# vape_v3_logic.net
KiCad netlist of a schematic drawn in EAGLE
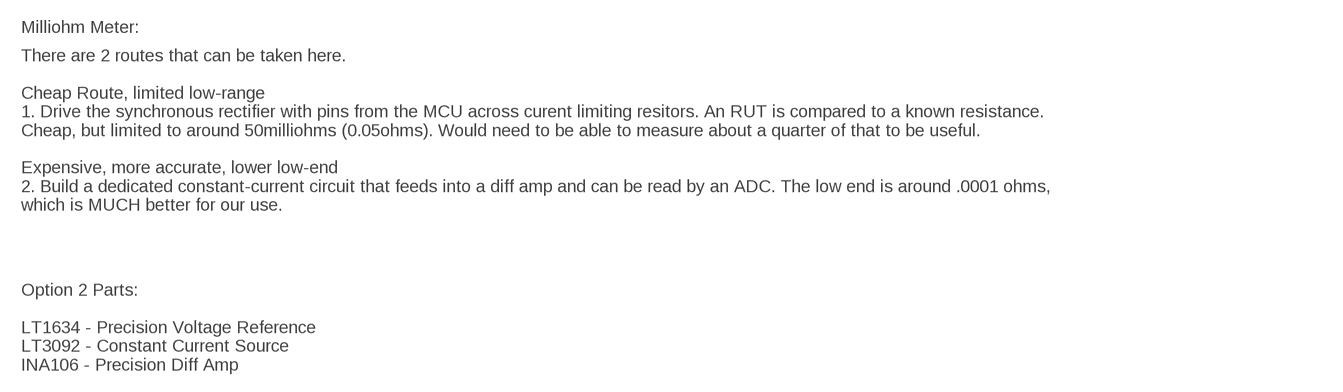
[diagram p0: schematic, sheet 1]
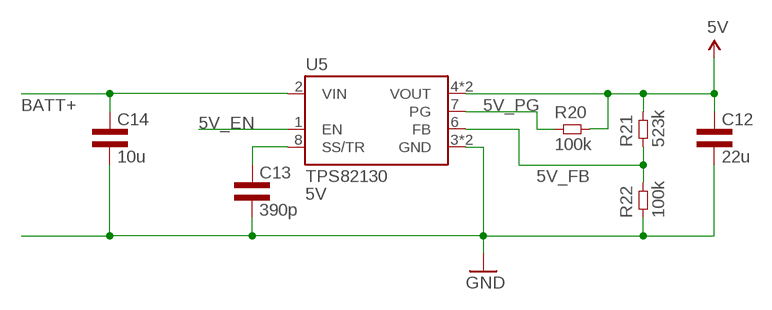
[diagram p1: schematic, sheet 2]
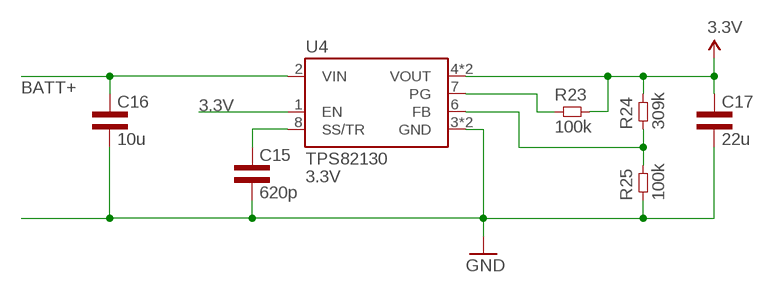
[diagram p2: schematic, sheet 3]
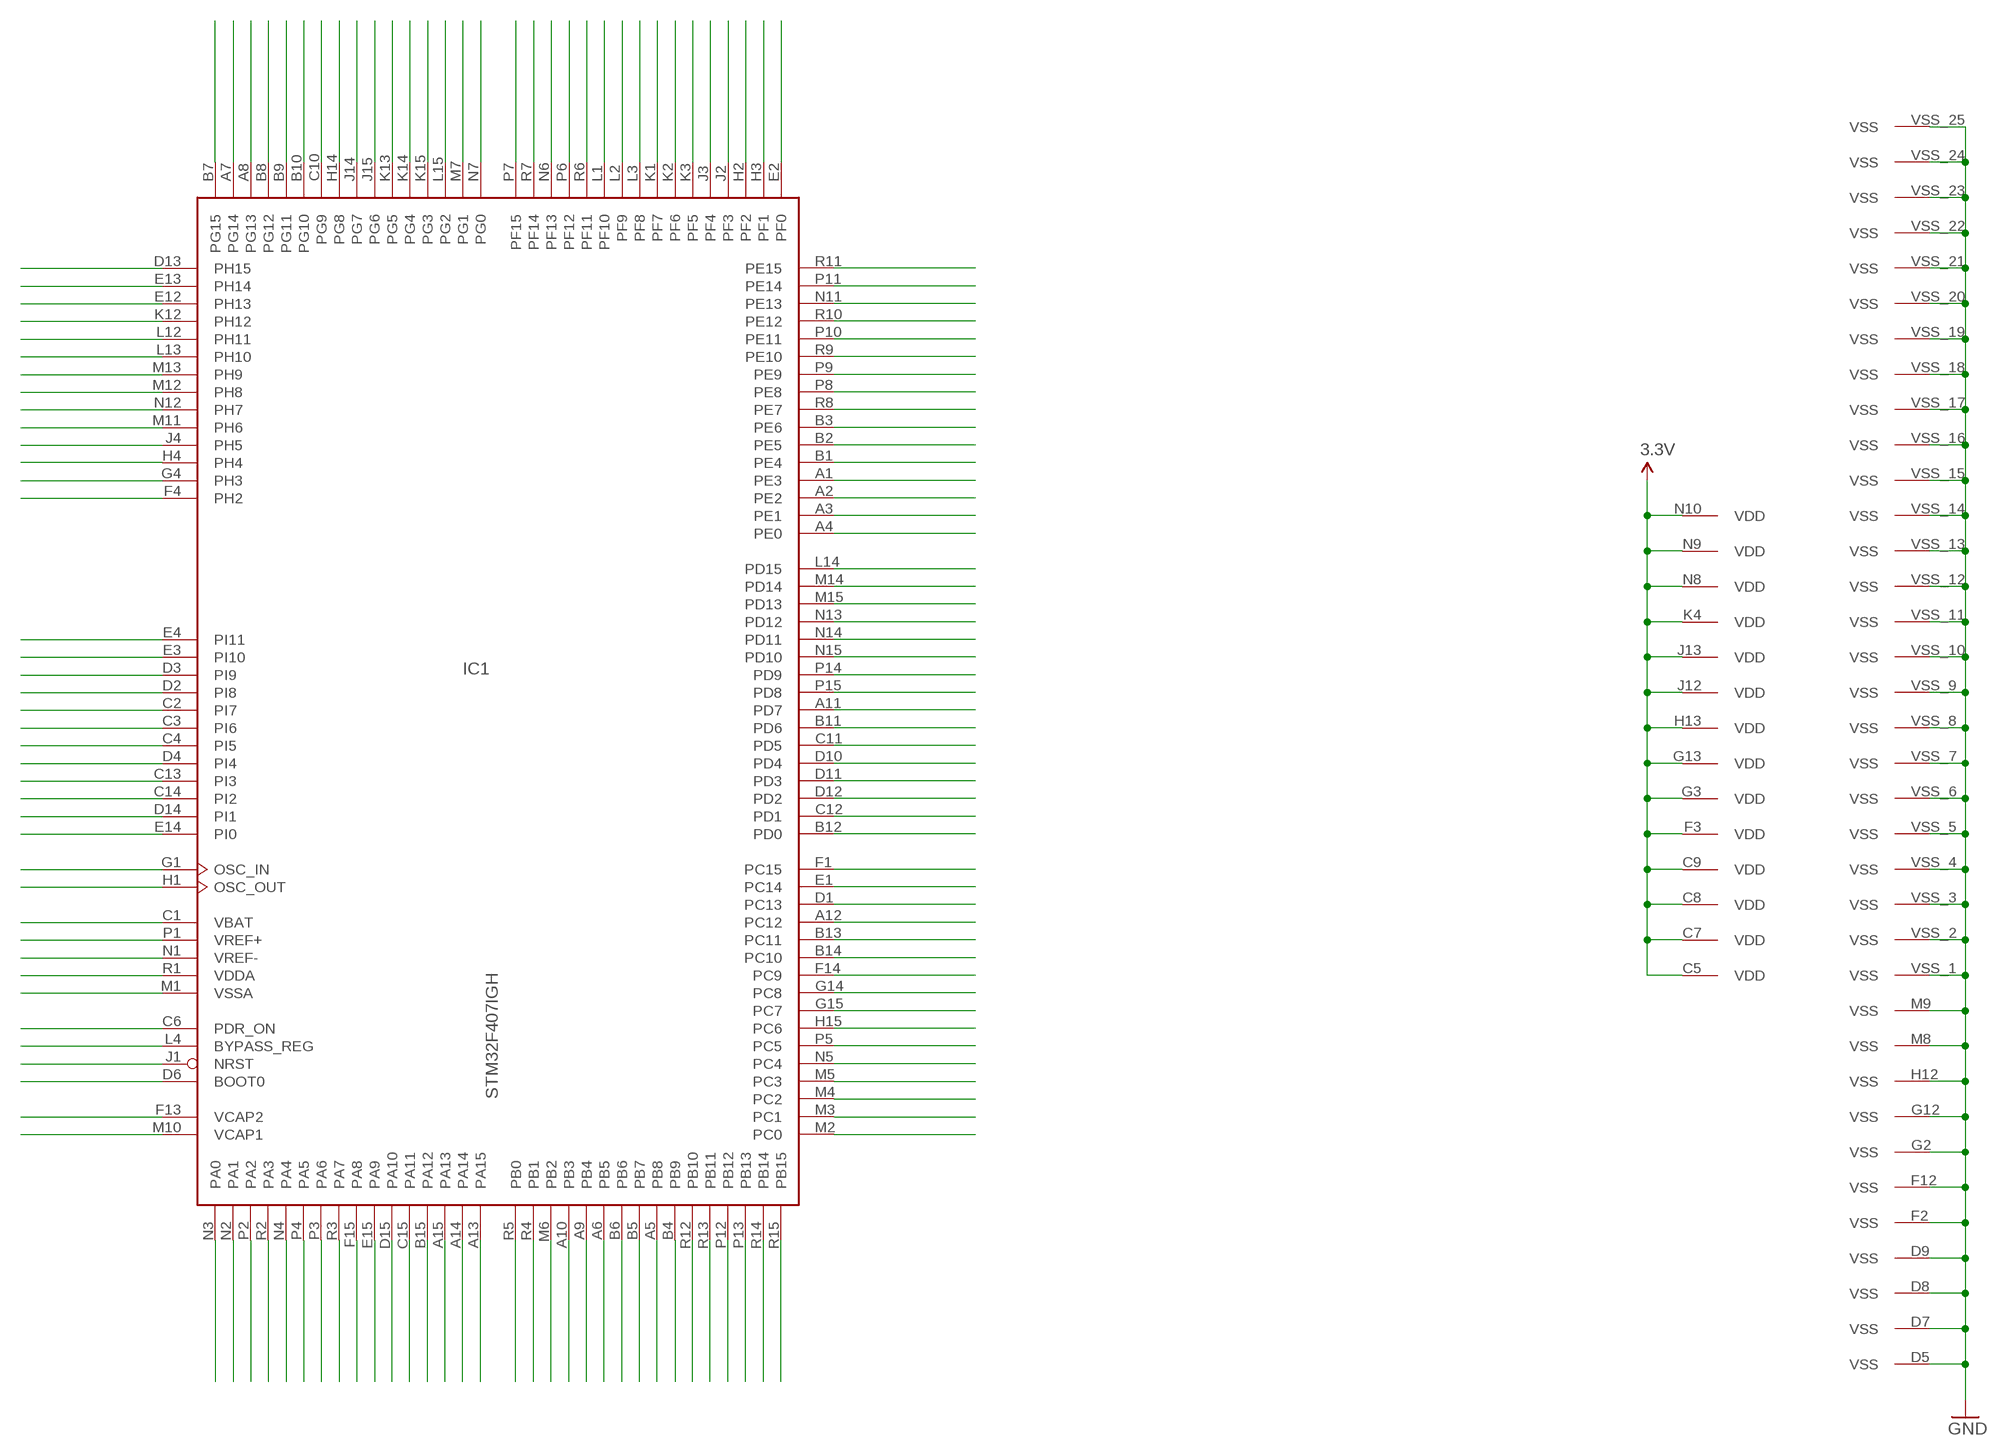
[diagram p3: schematic, sheet 4]
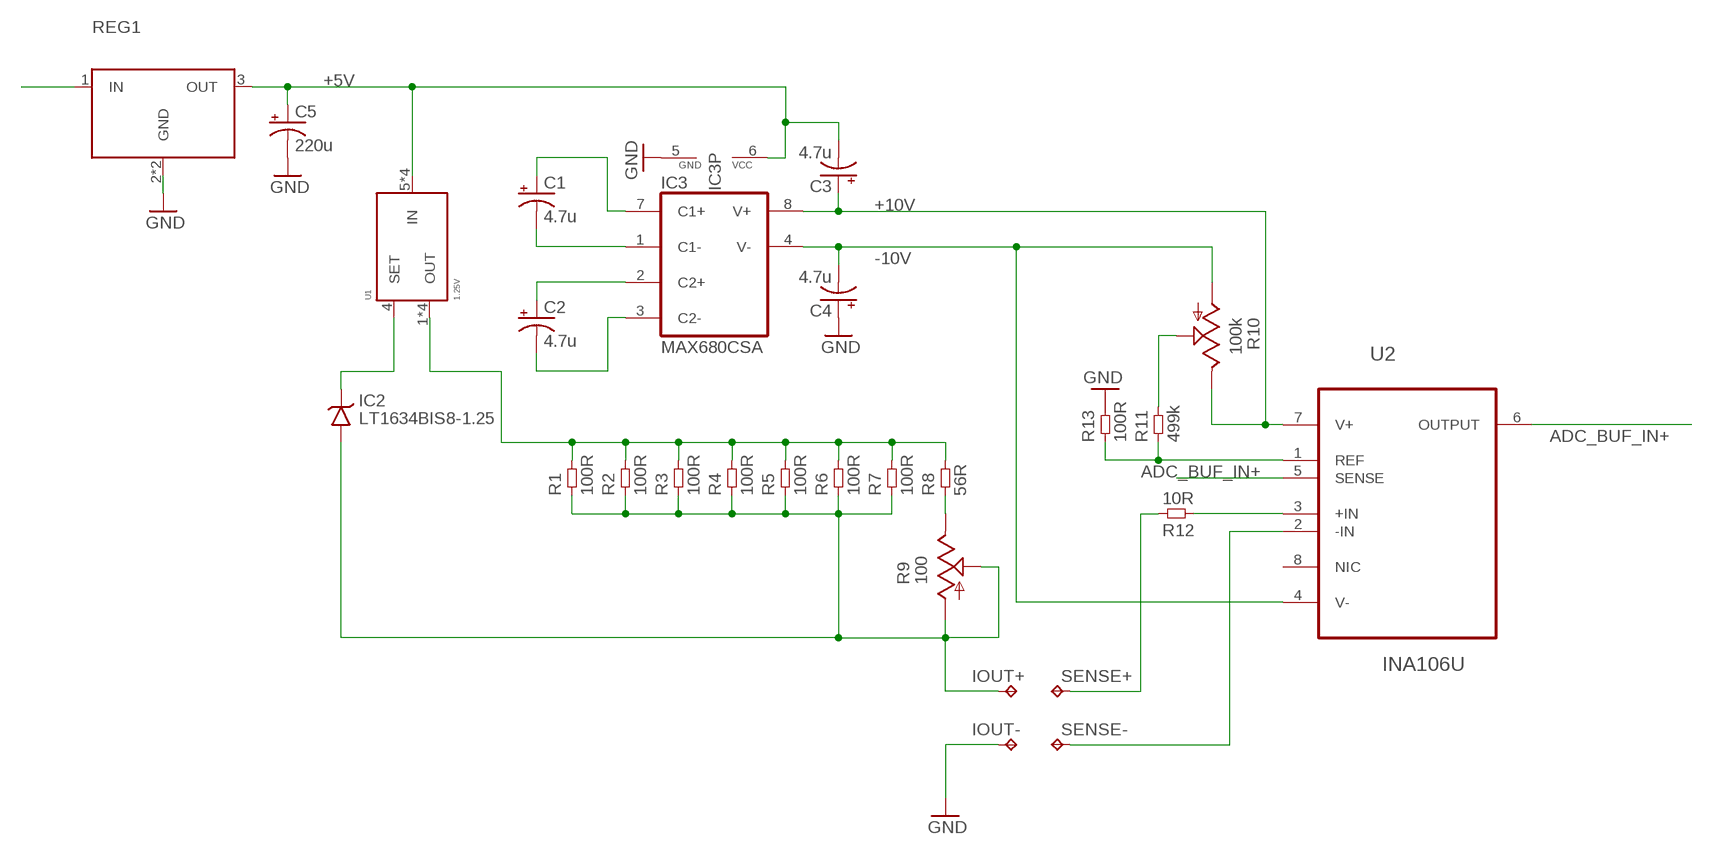
[diagram p4: schematic, sheet 5]
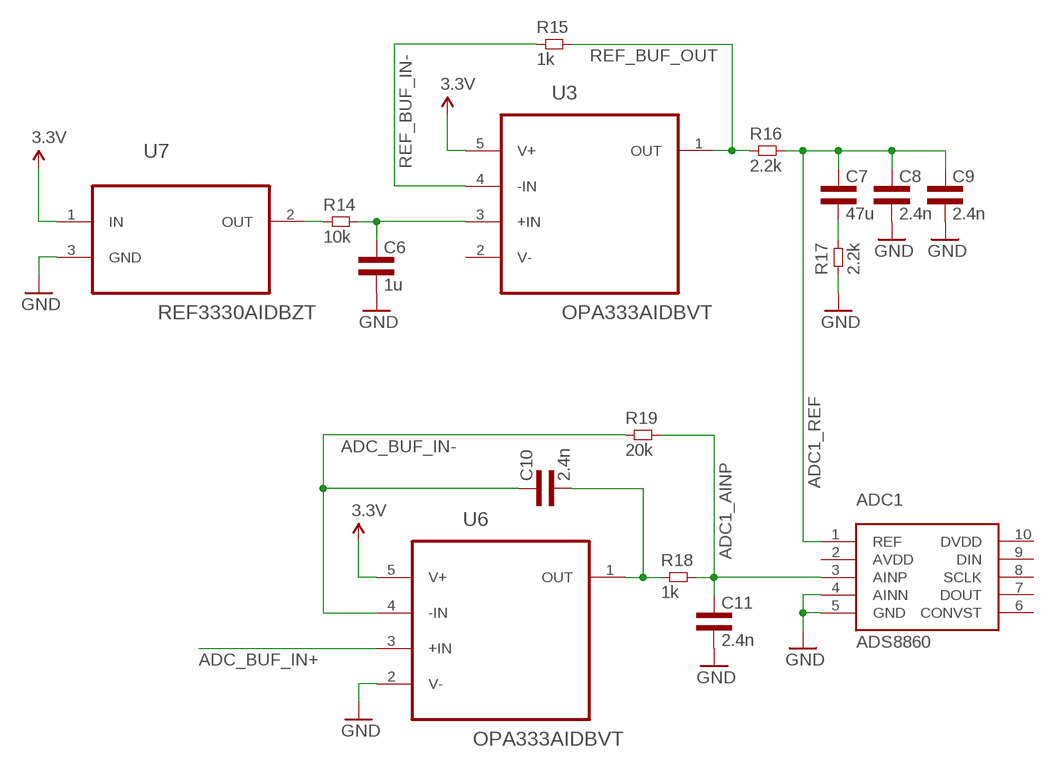
[diagram p5: schematic, sheet 6]
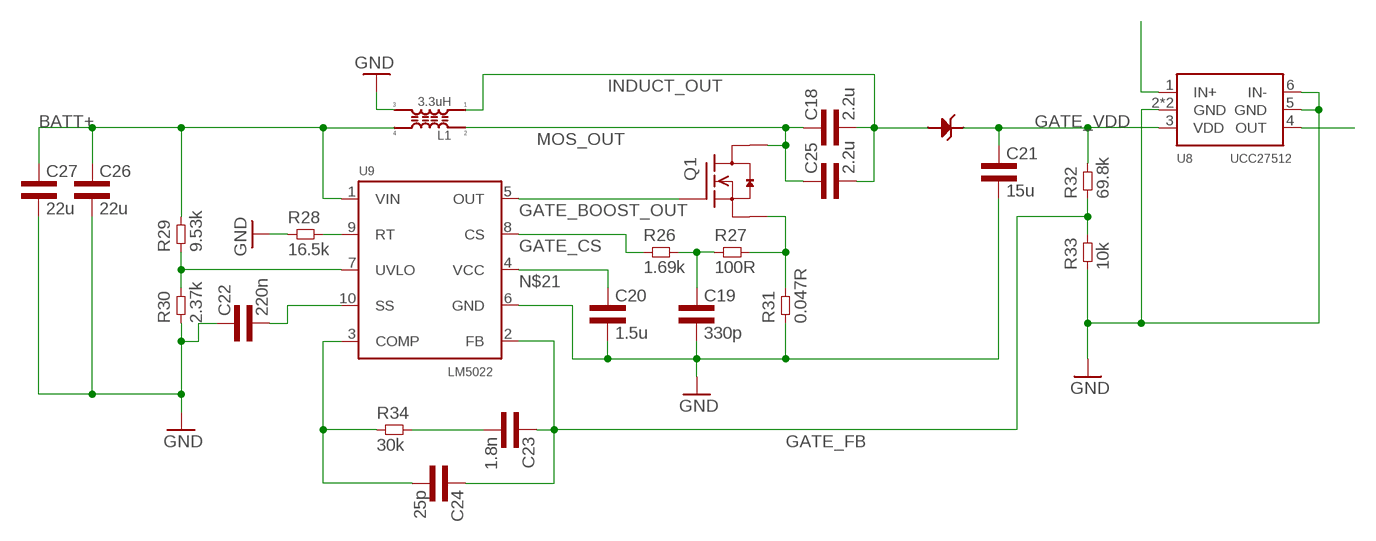
[diagram p6: schematic, sheet 7]

(export (version "E")
  (design (tool "Eeschema 10.0.6"))
  (components
    (comp (ref "IC1")
      (value "STM32F407IGH")
      (footprint "eagle-import:UFBGA176+25")
      (libsource (lib "eagle-import") (part "STM32F407IHG"))
    )
    (comp (ref "C1")
      (value "4.7u")
      (footprint "eagle-import:B_3528-21R")
      (fields (field (name "PART#") "T521B475M035ATE150"))
      (libsource (lib "eagle-import") (part "CPOL-USB/3528-21R"))
    )
    (comp (ref "C2")
      (value "4.7u")
      (footprint "eagle-import:B_3528-21R")
      (fields (field (name "PART#") "T521B475M035ATE150"))
      (libsource (lib "eagle-import") (part "CPOL-USB/3528-21R"))
    )
    (comp (ref "C3")
      (value "4.7u")
      (footprint "eagle-import:B_3528-21R")
      (fields (field (name "PART#") "T521B475M035ATE150"))
      (libsource (lib "eagle-import") (part "CPOL-USB/3528-21R"))
    )
    (comp (ref "C4")
      (value "4.7u")
      (footprint "eagle-import:B_3528-21R")
      (fields (field (name "PART#") "T521B475M035ATE150"))
      (libsource (lib "eagle-import") (part "CPOL-USB/3528-21R"))
    )
    (comp (ref "C5")
      (value "220u")
      (footprint "eagle-import:PANASONIC_C")
      (libsource (lib "eagle-import") (part "CPOL-USC"))
    )
    (comp (ref "IC2")
      (value "LT1634BIS8-1.25")
      (footprint "eagle-import:S8")
      (libsource (lib "eagle-import") (part "LT1634BIS8-1.25"))
    )
    (comp (ref "IC3")
      (value "MAX680CSA")
      (footprint "eagle-import:SO08")
      (fields (field (name "MF") "MAXIM"))
      (libsource (lib "eagle-import") (part "MAX680CSA"))
    )
    (comp (ref "IOUT+")
      (value "TPPAD1-17")
      (footprint "eagle-import:P1-17")
      (libsource (lib "eagle-import") (part "TPPAD1-17"))
    )
    (comp (ref "IOUT-")
      (value "TPPAD1-17")
      (footprint "eagle-import:P1-17")
      (libsource (lib "eagle-import") (part "TPPAD1-17"))
    )
    (comp (ref "R1")
      (value "100R")
      (footprint "eagle-import:0603L3")
      (fields (field (name "PART#") "APC0603T100RZ"))
      (libsource (lib "eagle-import") (part "RES0603L3"))
    )
    (comp (ref "R2")
      (value "100R")
      (footprint "eagle-import:0603L3")
      (fields (field (name "PART#") "APC0603T100RZ"))
      (libsource (lib "eagle-import") (part "RES0603L3"))
    )
    (comp (ref "R3")
      (value "100R")
      (footprint "eagle-import:0603L3")
      (fields (field (name "PART#") "APC0603T100RZ"))
      (libsource (lib "eagle-import") (part "RES0603L3"))
    )
    (comp (ref "R4")
      (value "100R")
      (footprint "eagle-import:0603L3")
      (fields (field (name "PART#") "APC0603T100RZ"))
      (libsource (lib "eagle-import") (part "RES0603L3"))
    )
    (comp (ref "R5")
      (value "100R")
      (footprint "eagle-import:0603L3")
      (fields (field (name "PART#") "APC0603T100RZ"))
      (libsource (lib "eagle-import") (part "RES0603L3"))
    )
    (comp (ref "R6")
      (value "100R")
      (footprint "eagle-import:0603L3")
      (fields (field (name "PART#") "APC0603T100RZ"))
      (libsource (lib "eagle-import") (part "RES0603L3"))
    )
    (comp (ref "R7")
      (value "100R")
      (footprint "eagle-import:0603L3")
      (fields (field (name "PART#") "APC0603T100RZ"))
      (libsource (lib "eagle-import") (part "RES0603L3"))
    )
    (comp (ref "R8")
      (value "56R")
      (footprint "eagle-import:0603L3")
      (fields (field (name "PART#") "APC0603T100RZ"))
      (libsource (lib "eagle-import") (part "RES0603L3"))
    )
    (comp (ref "R9")
      (value "100")
      (footprint "eagle-import:3223W")
      (libsource (lib "eagle-import") (part "TRIM_US-3223W"))
    )
    (comp (ref "R10")
      (value "100k")
      (footprint "eagle-import:3223W")
      (libsource (lib "eagle-import") (part "TRIM_US-3223W"))
    )
    (comp (ref "R11")
      (value "499k")
      (footprint "eagle-import:0603L3")
      (libsource (lib "eagle-import") (part "RES0603L3"))
    )
    (comp (ref "R12")
      (value "10R")
      (footprint "eagle-import:0603L3")
      (libsource (lib "eagle-import") (part "RES0603L3"))
    )
    (comp (ref "R13")
      (value "100R")
      (footprint "eagle-import:0603L3")
      (libsource (lib "eagle-import") (part "RES0603L3"))
    )
    (comp (ref "REG1")
      (value "LDO_REG_4PIN")
      (footprint "eagle-import:SOT-223-3")
      (libsource (lib "eagle-import") (part "LDO_REG_4PIN"))
    )
    (comp (ref "SENSE+")
      (value "TPPAD1-17")
      (footprint "eagle-import:P1-17")
      (libsource (lib "eagle-import") (part "TPPAD1-17"))
    )
    (comp (ref "SENSE-")
      (value "TPPAD1-17")
      (footprint "eagle-import:P1-17")
      (libsource (lib "eagle-import") (part "TPPAD1-17"))
    )
    (comp (ref "U1")
      (value "1.25V")
      (footprint "eagle-import:DD-8")
      (libsource (lib "eagle-import") (part "LT3092"))
    )
    (comp (ref "U2")
      (value "INA106U")
      (footprint "eagle-import:SOIC127P600X175-8N")
      (libsource (lib "eagle-import") (part "INA106U"))
    )
    (comp (ref "ADC1")
      (value "ADS8860IDGSR")
      (footprint "eagle-import:S-PDSO-G10")
      (libsource (lib "eagle-import") (part "ADS8860IDGSR"))
    )
    (comp (ref "C6")
      (value "1u")
      (footprint "eagle-import:0603L3")
      (libsource (lib "eagle-import") (part "CAP0603L3"))
    )
    (comp (ref "C7")
      (value "47u")
      (footprint "eagle-import:0805L3")
      (fields (field (name "PART#") "C2012JB1A476M125AC"))
      (libsource (lib "eagle-import") (part "CAP0805L3"))
    )
    (comp (ref "C8")
      (value "2.4n")
      (footprint "eagle-import:0603L3")
      (libsource (lib "eagle-import") (part "CAP0603L3"))
    )
    (comp (ref "C9")
      (value "2.4n")
      (footprint "eagle-import:0603L3")
      (libsource (lib "eagle-import") (part "CAP0603L3"))
    )
    (comp (ref "C10")
      (value "2.4n")
      (footprint "eagle-import:0603L3")
      (libsource (lib "eagle-import") (part "CAP0603L3"))
    )
    (comp (ref "C11")
      (value "2.4n")
      (footprint "eagle-import:0603L3")
      (libsource (lib "eagle-import") (part "CAP0603L3"))
    )
    (comp (ref "R14")
      (value "10k")
      (footprint "eagle-import:0603L3")
      (libsource (lib "eagle-import") (part "RES0603L3"))
    )
    (comp (ref "R15")
      (value "1k")
      (footprint "eagle-import:0603L3")
      (libsource (lib "eagle-import") (part "RES0603L3"))
    )
    (comp (ref "R16")
      (value "2.2k")
      (footprint "eagle-import:0603L3")
      (libsource (lib "eagle-import") (part "RES0603L3"))
    )
    (comp (ref "R17")
      (value "2.2k")
      (footprint "eagle-import:0603L3")
      (libsource (lib "eagle-import") (part "RES0603L3"))
    )
    (comp (ref "R18")
      (value "1k")
      (footprint "eagle-import:0603L3")
      (libsource (lib "eagle-import") (part "RES0603L3"))
    )
    (comp (ref "R19")
      (value "20k")
      (footprint "eagle-import:0603L3")
      (libsource (lib "eagle-import") (part "RES0603L3"))
    )
    (comp (ref "U3")
      (value "OPA333AIDBVT")
      (footprint "eagle-import:SOT95P280X145-5N")
      (libsource (lib "eagle-import") (part "OPA333AIDBVT"))
    )
    (comp (ref "U6")
      (value "OPA333AIDBVT")
      (footprint "eagle-import:SOT95P280X145-5N")
      (libsource (lib "eagle-import") (part "OPA333AIDBVT"))
    )
    (comp (ref "U7")
      (value "REF3330AIDBZT")
      (footprint "eagle-import:SOT95P237X112-3N")
      (libsource (lib "eagle-import") (part "REF3330AIDBZT"))
    )
    (comp (ref "C12")
      (value "22u")
      (footprint "eagle-import:1206L3")
      (libsource (lib "eagle-import") (part "CAP1206L3"))
    )
    (comp (ref "C13")
      (value "390p")
      (footprint "eagle-import:0603L3")
      (libsource (lib "eagle-import") (part "CAP0603L3"))
    )
    (comp (ref "C14")
      (value "10u")
      (footprint "eagle-import:0805L3")
      (libsource (lib "eagle-import") (part "CAP0805L3"))
    )
    (comp (ref "R20")
      (value "100k")
      (footprint "eagle-import:0805L3")
      (libsource (lib "eagle-import") (part "RES0805L3"))
    )
    (comp (ref "R21")
      (value "523k")
      (footprint "eagle-import:0603L3")
      (libsource (lib "eagle-import") (part "RES0603L3"))
    )
    (comp (ref "R22")
      (value "100k")
      (footprint "eagle-import:0603L3")
      (libsource (lib "eagle-import") (part "RES0603L3"))
    )
    (comp (ref "U5")
      (value "TPS82130")
      (footprint "eagle-import:SIL0008D")
      (fields (field (name "VOUT") "5V"))
      (libsource (lib "eagle-import") (part "TPS82130"))
    )
    (comp (ref "C15")
      (value "620p")
      (footprint "eagle-import:0603L3")
      (libsource (lib "eagle-import") (part "CAP0603L3"))
    )
    (comp (ref "C16")
      (value "10u")
      (footprint "eagle-import:0805L3")
      (libsource (lib "eagle-import") (part "CAP0805L3"))
    )
    (comp (ref "C17")
      (value "22u")
      (footprint "eagle-import:1206L3")
      (libsource (lib "eagle-import") (part "CAP1206L3"))
    )
    (comp (ref "R23")
      (value "100k")
      (footprint "eagle-import:0805L3")
      (libsource (lib "eagle-import") (part "RES0805L3"))
    )
    (comp (ref "R24")
      (value "309k")
      (footprint "eagle-import:0603L3")
      (libsource (lib "eagle-import") (part "RES0603L3"))
    )
    (comp (ref "R25")
      (value "100k")
      (footprint "eagle-import:0603L3")
      (libsource (lib "eagle-import") (part "RES0603L3"))
    )
    (comp (ref "U4")
      (value "TPS82130")
      (footprint "eagle-import:SIL0008D")
      (fields (field (name "VOUT") "3.3V"))
      (libsource (lib "eagle-import") (part "TPS82130"))
    )
    (comp (ref "C18")
      (value "2.2u")
      (footprint "eagle-import:0402L3")
      (libsource (lib "eagle-import") (part "CAP0402L3"))
    )
    (comp (ref "C19")
      (value "330p")
      (footprint "eagle-import:0402L3")
      (libsource (lib "eagle-import") (part "CAP0402L3"))
    )
    (comp (ref "C20")
      (value "1.5u")
      (footprint "eagle-import:0402L3")
      (libsource (lib "eagle-import") (part "CAP0402L3"))
    )
    (comp (ref "C21")
      (value "15u")
      (footprint "eagle-import:1206L3")
      (libsource (lib "eagle-import") (part "CAP1206L3"))
    )
    (comp (ref "C22")
      (value "220n")
      (footprint "eagle-import:0402L3")
      (libsource (lib "eagle-import") (part "CAP0402L3"))
    )
    (comp (ref "C23")
      (value "1.8n")
      (footprint "eagle-import:0402L3")
      (libsource (lib "eagle-import") (part "CAP0402L3"))
    )
    (comp (ref "C24")
      (value "25p")
      (footprint "eagle-import:0402L3")
      (libsource (lib "eagle-import") (part "CAP0402L3"))
    )
    (comp (ref "C25")
      (value "2.2u")
      (footprint "eagle-import:0402L3")
      (libsource (lib "eagle-import") (part "CAP0402L3"))
    )
    (comp (ref "C26")
      (value "22u")
      (footprint "eagle-import:1206L3")
      (libsource (lib "eagle-import") (part "CAP1206L3"))
    )
    (comp (ref "C27")
      (value "22u")
      (footprint "eagle-import:1206L3")
      (libsource (lib "eagle-import") (part "CAP1206L3"))
    )
    (comp (ref "D1")
      (value ".77V / 5.5A")
      (footprint "eagle-import:DPAK")
      (libsource (lib "eagle-import") (part "SCHOTTKYDIODEDPAK"))
    )
    (comp (ref "L1")
      (value "3.3uH")
      (footprint "eagle-import:DRQ12X")
      (libsource (lib "eagle-import") (part "DRQ127"))
    )
    (comp (ref "Q1")
      (value "OPEN-BLDC_FDMC7664")
      (footprint "eagle-import:OPEN-BLDC_MLP33")
      (libsource (lib "eagle-import") (part "OPEN-BLDC_FDMC7664"))
    )
    (comp (ref "R26")
      (value "1.69k")
      (footprint "eagle-import:0402L3")
      (libsource (lib "eagle-import") (part "RES0402L3"))
    )
    (comp (ref "R27")
      (value "100R")
      (footprint "eagle-import:0402L3")
      (libsource (lib "eagle-import") (part "RES0402L3"))
    )
    (comp (ref "R28")
      (value "16.5k")
      (footprint "eagle-import:0402L3")
      (libsource (lib "eagle-import") (part "RES0402L3"))
    )
    (comp (ref "R29")
      (value "9.53k")
      (footprint "eagle-import:0402L3")
      (libsource (lib "eagle-import") (part "RES0402L3"))
    )
    (comp (ref "R30")
      (value "2.37k")
      (footprint "eagle-import:0402L3")
      (libsource (lib "eagle-import") (part "RES0402L3"))
    )
    (comp (ref "R31")
      (value "0.047R")
      (footprint "eagle-import:1206L3")
      (libsource (lib "eagle-import") (part "RES1206L3"))
    )
    (comp (ref "R32")
      (value "69.8k")
      (footprint "eagle-import:0402L3")
      (libsource (lib "eagle-import") (part "RES0402L3"))
    )
    (comp (ref "R33")
      (value "10k")
      (footprint "eagle-import:0402L3")
      (libsource (lib "eagle-import") (part "RES0402L3"))
    )
    (comp (ref "R34")
      (value "30k")
      (footprint "eagle-import:0402L3")
      (libsource (lib "eagle-import") (part "RES0402L3"))
    )
    (comp (ref "U8")
      (value "UCC27512")
      (footprint "eagle-import:S-PWSON-N6")
      (libsource (lib "eagle-import") (part "UCC27512"))
    )
    (comp (ref "U9")
      (value "LM5022")
      (footprint "eagle-import:S-PDSO-G10")
      (libsource (lib "eagle-import") (part "LM5022"))
    )
  )
  (nets
    (net (code "1") (name "+5V") (class "Default")
      (node (ref "C3") (pin "-") (pinfunction "-_-") (pintype "passive"))
      (node (ref "C5") (pin "+") (pinfunction "+_+") (pintype "passive"))
      (node (ref "IC3") (pin "6") (pinfunction "VCC_6") (pintype "power_in"))
      (node (ref "REG1") (pin "3") (pinfunction "OUT_3") (pintype "bidirectional"))
      (node (ref "U1") (pin "5") (pinfunction "IN_5") (pintype "bidirectional"))
      (node (ref "U1") (pin "6") (pinfunction "IN_6") (pintype "bidirectional"))
      (node (ref "U1") (pin "7") (pinfunction "IN_7") (pintype "bidirectional"))
      (node (ref "U1") (pin "8") (pinfunction "IN_8") (pintype "bidirectional"))
    )
    (net (code "2") (name "+10V") (class "Default")
      (node (ref "C3") (pin "+") (pinfunction "+_+") (pintype "passive"))
      (node (ref "IC3") (pin "8") (pinfunction "V+_8") (pintype "output"))
      (node (ref "R10") (pin "3") (pinfunction "E_3") (pintype "passive"))
      (node (ref "U2") (pin "7") (pinfunction "V+_7") (pintype "power_in"))
    )
    (net (code "3") (name "-10V") (class "Default")
      (node (ref "C4") (pin "-") (pinfunction "-_-") (pintype "passive"))
      (node (ref "IC3") (pin "4") (pinfunction "V-_4") (pintype "output"))
      (node (ref "R10") (pin "1") (pinfunction "A_1") (pintype "passive"))
      (node (ref "U2") (pin "4") (pinfunction "V-_4") (pintype "power_in"))
    )
    (net (code "4") (name "3.3V") (class "Default")
      (node (ref "C17") (pin "1") (pinfunction "1_1") (pintype "bidirectional"))
      (node (ref "IC1") (pin "C5") (pinfunction "VDD_C5") (pintype "power_in"))
      (node (ref "IC1") (pin "C7") (pinfunction "VDD_C7") (pintype "power_in"))
      (node (ref "IC1") (pin "C8") (pinfunction "VDD_C8") (pintype "power_in"))
      (node (ref "IC1") (pin "C9") (pinfunction "VDD_C9") (pintype "power_in"))
      (node (ref "IC1") (pin "F3") (pinfunction "VDD_F3") (pintype "power_in"))
      (node (ref "IC1") (pin "G13") (pinfunction "VDD_G13") (pintype "power_in"))
      (node (ref "IC1") (pin "G3") (pinfunction "VDD_G3") (pintype "power_in"))
      (node (ref "IC1") (pin "H13") (pinfunction "VDD_H13") (pintype "power_in"))
      (node (ref "IC1") (pin "J12") (pinfunction "VDD_J12") (pintype "power_in"))
      (node (ref "IC1") (pin "J13") (pinfunction "VDD_J13") (pintype "power_in"))
      (node (ref "IC1") (pin "K4") (pinfunction "VDD_K4") (pintype "power_in"))
      (node (ref "IC1") (pin "N10") (pinfunction "VDD_N10") (pintype "power_in"))
      (node (ref "IC1") (pin "N8") (pinfunction "VDD_N8") (pintype "power_in"))
      (node (ref "IC1") (pin "N9") (pinfunction "VDD_N9") (pintype "power_in"))
      (node (ref "R23") (pin "2") (pinfunction "2_2") (pintype "bidirectional"))
      (node (ref "R24") (pin "P$2") (pinfunction "2_P$2") (pintype "bidirectional"))
      (node (ref "U3") (pin "5") (pinfunction "V+_5") (pintype "power_in"))
      (node (ref "U4") (pin "1") (pinfunction "EN_1") (pintype "bidirectional"))
      (node (ref "U4") (pin "4") (pinfunction "VOUT_4") (pintype "bidirectional"))
      (node (ref "U4") (pin "5") (pinfunction "VOUT_5") (pintype "bidirectional"))
      (node (ref "U6") (pin "5") (pinfunction "V+_5") (pintype "power_in"))
      (node (ref "U7") (pin "1") (pinfunction "IN_1") (pintype "power_in"))
    )
    (net (code "5") (name "5V") (class "Default")
      (node (ref "C12") (pin "1") (pinfunction "1_1") (pintype "bidirectional"))
      (node (ref "R20") (pin "2") (pinfunction "2_2") (pintype "bidirectional"))
      (node (ref "R21") (pin "P$2") (pinfunction "2_P$2") (pintype "bidirectional"))
      (node (ref "U5") (pin "4") (pinfunction "VOUT_4") (pintype "bidirectional"))
      (node (ref "U5") (pin "5") (pinfunction "VOUT_5") (pintype "bidirectional"))
    )
    (net (code "6") (name "5V_EN") (class "Default")
      (node (ref "U5") (pin "1") (pinfunction "EN_1") (pintype "bidirectional"))
    )
    (net (code "7") (name "5V_FB") (class "Default")
      (node (ref "R21") (pin "P$1") (pinfunction "1_P$1") (pintype "bidirectional"))
      (node (ref "R22") (pin "P$2") (pinfunction "2_P$2") (pintype "bidirectional"))
      (node (ref "U5") (pin "6") (pinfunction "FB_6") (pintype "bidirectional"))
    )
    (net (code "8") (name "5V_PG") (class "Default")
      (node (ref "R20") (pin "1") (pinfunction "1_1") (pintype "bidirectional"))
      (node (ref "U5") (pin "7") (pinfunction "PG_7") (pintype "bidirectional"))
    )
    (net (code "9") (name "ADC1_AINP") (class "Default")
      (node (ref "ADC1") (pin "3") (pinfunction "AINP_3") (pintype "bidirectional"))
      (node (ref "C11") (pin "P$1") (pinfunction "1_P$1") (pintype "bidirectional"))
      (node (ref "R18") (pin "P$2") (pinfunction "2_P$2") (pintype "bidirectional"))
      (node (ref "R19") (pin "P$2") (pinfunction "2_P$2") (pintype "bidirectional"))
    )
    (net (code "10") (name "ADC1_REF") (class "Default")
      (node (ref "ADC1") (pin "1") (pinfunction "REF_1") (pintype "bidirectional"))
      (node (ref "C7") (pin "1") (pinfunction "1_1") (pintype "bidirectional"))
      (node (ref "C8") (pin "P$1") (pinfunction "1_P$1") (pintype "bidirectional"))
      (node (ref "C9") (pin "P$1") (pinfunction "1_P$1") (pintype "bidirectional"))
      (node (ref "R16") (pin "P$2") (pinfunction "2_P$2") (pintype "bidirectional"))
    )
    (net (code "11") (name "ADC_BUF_IN+") (class "Default")
      (node (ref "U2") (pin "5") (pinfunction "SENSE_5") (pintype "input"))
      (node (ref "U2") (pin "6") (pinfunction "OUTPUT_6") (pintype "output"))
      (node (ref "U6") (pin "3") (pinfunction "+IN_3") (pintype "input"))
    )
    (net (code "12") (name "ADC_BUF_IN-") (class "Default")
      (node (ref "C10") (pin "P$1") (pinfunction "1_P$1") (pintype "bidirectional"))
      (node (ref "R19") (pin "P$1") (pinfunction "1_P$1") (pintype "bidirectional"))
      (node (ref "U6") (pin "4") (pinfunction "-IN_4") (pintype "input"))
    )
    (net (code "13") (name "BATT+") (class "Default")
      (node (ref "C14") (pin "1") (pinfunction "1_1") (pintype "bidirectional"))
      (node (ref "C16") (pin "1") (pinfunction "1_1") (pintype "bidirectional"))
      (node (ref "C26") (pin "1") (pinfunction "1_1") (pintype "bidirectional"))
      (node (ref "C27") (pin "1") (pinfunction "1_1") (pintype "bidirectional"))
      (node (ref "L1") (pin "4") (pinfunction "4_4") (pintype "bidirectional"))
      (node (ref "R29") (pin "P$2") (pinfunction "2_P$2") (pintype "bidirectional"))
      (node (ref "U4") (pin "2") (pinfunction "VIN_2") (pintype "bidirectional"))
      (node (ref "U5") (pin "2") (pinfunction "VIN_2") (pintype "bidirectional"))
      (node (ref "U9") (pin "1") (pinfunction "VIN_1") (pintype "bidirectional"))
    )
    (net (code "14") (name "GATE_BOOST_OUT") (class "Default")
      (node (ref "Q1") (pin "4G") (pinfunction "G_4G") (pintype "passive"))
      (node (ref "U9") (pin "5") (pinfunction "OUT_5") (pintype "bidirectional"))
    )
    (net (code "15") (name "GATE_CS") (class "Default")
      (node (ref "R26") (pin "P$1") (pinfunction "1_P$1") (pintype "bidirectional"))
      (node (ref "U9") (pin "8") (pinfunction "CS_8") (pintype "bidirectional"))
    )
    (net (code "16") (name "GATE_FB") (class "Default")
      (node (ref "C23") (pin "P$1") (pinfunction "1_P$1") (pintype "bidirectional"))
      (node (ref "C24") (pin "P$1") (pinfunction "1_P$1") (pintype "bidirectional"))
      (node (ref "R32") (pin "P$1") (pinfunction "1_P$1") (pintype "bidirectional"))
      (node (ref "R33") (pin "P$2") (pinfunction "2_P$2") (pintype "bidirectional"))
      (node (ref "U9") (pin "2") (pinfunction "FB_2") (pintype "bidirectional"))
    )
    (net (code "17") (name "GATE_VDD") (class "Default")
      (node (ref "C21") (pin "1") (pinfunction "1_1") (pintype "bidirectional"))
      (node (ref "D1") (pin "TAB") (pinfunction "CATHODE_TAB") (pintype "bidirectional"))
      (node (ref "R32") (pin "P$2") (pinfunction "2_P$2") (pintype "bidirectional"))
      (node (ref "U8") (pin "3") (pinfunction "VDD_3") (pintype "bidirectional"))
    )
    (net (code "18") (name "GND") (class "Default")
      (node (ref "ADC1") (pin "4") (pinfunction "AINN_4") (pintype "bidirectional"))
      (node (ref "ADC1") (pin "5") (pinfunction "GND_5") (pintype "bidirectional"))
      (node (ref "C11") (pin "P$2") (pinfunction "2_P$2") (pintype "bidirectional"))
      (node (ref "C12") (pin "2") (pinfunction "2_2") (pintype "bidirectional"))
      (node (ref "C13") (pin "P$2") (pinfunction "2_P$2") (pintype "bidirectional"))
      (node (ref "C14") (pin "2") (pinfunction "2_2") (pintype "bidirectional"))
      (node (ref "C15") (pin "P$2") (pinfunction "2_P$2") (pintype "bidirectional"))
      (node (ref "C16") (pin "2") (pinfunction "2_2") (pintype "bidirectional"))
      (node (ref "C17") (pin "2") (pinfunction "2_2") (pintype "bidirectional"))
      (node (ref "C19") (pin "P$2") (pinfunction "2_P$2") (pintype "bidirectional"))
      (node (ref "C20") (pin "P$2") (pinfunction "2_P$2") (pintype "bidirectional"))
      (node (ref "C21") (pin "2") (pinfunction "2_2") (pintype "bidirectional"))
      (node (ref "C22") (pin "P$1") (pinfunction "1_P$1") (pintype "bidirectional"))
      (node (ref "C26") (pin "2") (pinfunction "2_2") (pintype "bidirectional"))
      (node (ref "C27") (pin "2") (pinfunction "2_2") (pintype "bidirectional"))
      (node (ref "C4") (pin "+") (pinfunction "+_+") (pintype "passive"))
      (node (ref "C5") (pin "-") (pinfunction "-_-") (pintype "passive"))
      (node (ref "C6") (pin "P$2") (pinfunction "2_P$2") (pintype "bidirectional"))
      (node (ref "C8") (pin "P$2") (pinfunction "2_P$2") (pintype "bidirectional"))
      (node (ref "C9") (pin "P$2") (pinfunction "2_P$2") (pintype "bidirectional"))
      (node (ref "IC1") (pin "D5") (pinfunction "VSS_D5") (pintype "power_in"))
      (node (ref "IC1") (pin "D7") (pinfunction "VSS_D7") (pintype "power_in"))
      (node (ref "IC1") (pin "D8") (pinfunction "VSS_D8") (pintype "power_in"))
      (node (ref "IC1") (pin "D9") (pinfunction "VSS_D9") (pintype "power_in"))
      (node (ref "IC1") (pin "F12") (pinfunction "VSS_F12") (pintype "power_in"))
      (node (ref "IC1") (pin "F2") (pinfunction "VSS_F2") (pintype "power_in"))
      (node (ref "IC1") (pin "G12") (pinfunction "VSS_G12") (pintype "power_in"))
      (node (ref "IC1") (pin "G2") (pinfunction "VSS_G2") (pintype "power_in"))
      (node (ref "IC1") (pin "H12") (pinfunction "VSS_H12") (pintype "power_in"))
      (node (ref "IC1") (pin "M8") (pinfunction "VSS_M8") (pintype "power_in"))
      (node (ref "IC1") (pin "M9") (pinfunction "VSS_M9") (pintype "power_in"))
      (node (ref "IC1") (pin "VSS_1") (pinfunction "VSS_VSS_1") (pintype "power_in"))
      (node (ref "IC1") (pin "VSS_10") (pinfunction "VSS_VSS_10") (pintype "power_in"))
      (node (ref "IC1") (pin "VSS_11") (pinfunction "VSS_VSS_11") (pintype "power_in"))
      (node (ref "IC1") (pin "VSS_12") (pinfunction "VSS_VSS_12") (pintype "power_in"))
      (node (ref "IC1") (pin "VSS_13") (pinfunction "VSS_VSS_13") (pintype "power_in"))
      (node (ref "IC1") (pin "VSS_14") (pinfunction "VSS_VSS_14") (pintype "power_in"))
      (node (ref "IC1") (pin "VSS_15") (pinfunction "VSS_VSS_15") (pintype "power_in"))
      (node (ref "IC1") (pin "VSS_16") (pinfunction "VSS_VSS_16") (pintype "power_in"))
      (node (ref "IC1") (pin "VSS_17") (pinfunction "VSS_VSS_17") (pintype "power_in"))
      (node (ref "IC1") (pin "VSS_18") (pinfunction "VSS_VSS_18") (pintype "power_in"))
      (node (ref "IC1") (pin "VSS_19") (pinfunction "VSS_VSS_19") (pintype "power_in"))
      (node (ref "IC1") (pin "VSS_2") (pinfunction "VSS_VSS_2") (pintype "power_in"))
      (node (ref "IC1") (pin "VSS_20") (pinfunction "VSS_VSS_20") (pintype "power_in"))
      (node (ref "IC1") (pin "VSS_21") (pinfunction "VSS_VSS_21") (pintype "power_in"))
      (node (ref "IC1") (pin "VSS_22") (pinfunction "VSS_VSS_22") (pintype "power_in"))
      (node (ref "IC1") (pin "VSS_23") (pinfunction "VSS_VSS_23") (pintype "power_in"))
      (node (ref "IC1") (pin "VSS_24") (pinfunction "VSS_VSS_24") (pintype "power_in"))
      (node (ref "IC1") (pin "VSS_25") (pinfunction "VSS_VSS_25") (pintype "power_in"))
      (node (ref "IC1") (pin "VSS_3") (pinfunction "VSS_VSS_3") (pintype "power_in"))
      (node (ref "IC1") (pin "VSS_4") (pinfunction "VSS_VSS_4") (pintype "power_in"))
      (node (ref "IC1") (pin "VSS_5") (pinfunction "VSS_VSS_5") (pintype "power_in"))
      (node (ref "IC1") (pin "VSS_6") (pinfunction "VSS_VSS_6") (pintype "power_in"))
      (node (ref "IC1") (pin "VSS_7") (pinfunction "VSS_VSS_7") (pintype "power_in"))
      (node (ref "IC1") (pin "VSS_8") (pinfunction "VSS_VSS_8") (pintype "power_in"))
      (node (ref "IC1") (pin "VSS_9") (pinfunction "VSS_VSS_9") (pintype "power_in"))
      (node (ref "IC3") (pin "5") (pinfunction "GND_5") (pintype "power_in"))
      (node (ref "IOUT-") (pin "TP") (pinfunction "TP_TP") (pintype "input"))
      (node (ref "L1") (pin "3") (pinfunction "3_3") (pintype "bidirectional"))
      (node (ref "R13") (pin "P$2") (pinfunction "2_P$2") (pintype "bidirectional"))
      (node (ref "R17") (pin "P$1") (pinfunction "1_P$1") (pintype "bidirectional"))
      (node (ref "R22") (pin "P$1") (pinfunction "1_P$1") (pintype "bidirectional"))
      (node (ref "R25") (pin "P$1") (pinfunction "1_P$1") (pintype "bidirectional"))
      (node (ref "R28") (pin "P$1") (pinfunction "1_P$1") (pintype "bidirectional"))
      (node (ref "R30") (pin "P$1") (pinfunction "1_P$1") (pintype "bidirectional"))
      (node (ref "R31") (pin "1") (pinfunction "1_1") (pintype "bidirectional"))
      (node (ref "R33") (pin "P$1") (pinfunction "1_P$1") (pintype "bidirectional"))
      (node (ref "REG1") (pin "2") (pinfunction "GND_2") (pintype "bidirectional"))
      (node (ref "REG1") (pin "4") (pinfunction "GND_4") (pintype "bidirectional"))
      (node (ref "U4") (pin "3") (pinfunction "GND_3") (pintype "bidirectional"))
      (node (ref "U4") (pin "TP") (pinfunction "GND_TP") (pintype "bidirectional"))
      (node (ref "U5") (pin "3") (pinfunction "GND_3") (pintype "bidirectional"))
      (node (ref "U5") (pin "TP") (pinfunction "GND_TP") (pintype "bidirectional"))
      (node (ref "U6") (pin "2") (pinfunction "V-_2") (pintype "power_in"))
      (node (ref "U7") (pin "3") (pinfunction "GND_3") (pintype "passive"))
      (node (ref "U8") (pin "2") (pinfunction "GND_2") (pintype "bidirectional"))
      (node (ref "U8") (pin "5") (pinfunction "GND_5") (pintype "bidirectional"))
      (node (ref "U8") (pin "6") (pinfunction "IN-_6") (pintype "bidirectional"))
      (node (ref "U8") (pin "TP") (pinfunction "GND_TP") (pintype "bidirectional"))
      (node (ref "U9") (pin "6") (pinfunction "GND_6") (pintype "bidirectional"))
    )
    (net (code "19") (name "INDUCT_OUT") (class "Default")
      (node (ref "C18") (pin "P$2") (pinfunction "2_P$2") (pintype "bidirectional"))
      (node (ref "C25") (pin "P$2") (pinfunction "2_P$2") (pintype "bidirectional"))
      (node (ref "D1") (pin "1") (pinfunction "ANODE_1") (pintype "bidirectional"))
      (node (ref "D1") (pin "3") (pinfunction "ANODE_3") (pintype "bidirectional"))
      (node (ref "L1") (pin "1") (pinfunction "1_1") (pintype "bidirectional"))
    )
    (net (code "20") (name "MOS_OUT") (class "Default")
      (node (ref "C18") (pin "P$1") (pinfunction "1_P$1") (pintype "bidirectional"))
      (node (ref "C25") (pin "P$1") (pinfunction "1_P$1") (pintype "bidirectional"))
      (node (ref "L1") (pin "2") (pinfunction "2_2") (pintype "bidirectional"))
      (node (ref "Q1") (pin "5678D") (pinfunction "D_5678D") (pintype "passive"))
    )
    (net (code "21") (name "N$21") (class "Default")
      (node (ref "C20") (pin "P$1") (pinfunction "1_P$1") (pintype "bidirectional"))
      (node (ref "U9") (pin "4") (pinfunction "VCC_4") (pintype "bidirectional"))
    )
    (net (code "22") (name "Net-(C6-1)") (class "Default")
      (node (ref "C6") (pin "P$1") (pinfunction "1_P$1") (pintype "bidirectional"))
      (node (ref "R14") (pin "P$2") (pinfunction "2_P$2") (pintype "bidirectional"))
      (node (ref "U3") (pin "3") (pinfunction "+IN_3") (pintype "input"))
    )
    (net (code "23") (name "Net-(C10-2)") (class "Default")
      (node (ref "C10") (pin "P$2") (pinfunction "2_P$2") (pintype "bidirectional"))
      (node (ref "R18") (pin "P$1") (pinfunction "1_P$1") (pintype "bidirectional"))
      (node (ref "U6") (pin "1") (pinfunction "OUT_1") (pintype "output"))
    )
    (net (code "24") (name "Net-(C13-1)") (class "Default")
      (node (ref "C13") (pin "P$1") (pinfunction "1_P$1") (pintype "bidirectional"))
      (node (ref "U5") (pin "8") (pinfunction "SS/TR_8") (pintype "bidirectional"))
    )
    (net (code "25") (name "Net-(C15-1)") (class "Default")
      (node (ref "C15") (pin "P$1") (pinfunction "1_P$1") (pintype "bidirectional"))
      (node (ref "U4") (pin "8") (pinfunction "SS/TR_8") (pintype "bidirectional"))
    )
    (net (code "26") (name "Net-(C19-1)") (class "Default")
      (node (ref "C19") (pin "P$1") (pinfunction "1_P$1") (pintype "bidirectional"))
      (node (ref "R26") (pin "P$2") (pinfunction "2_P$2") (pintype "bidirectional"))
      (node (ref "R27") (pin "P$1") (pinfunction "1_P$1") (pintype "bidirectional"))
    )
    (net (code "27") (name "Net-(C22-2)") (class "Default")
      (node (ref "C22") (pin "P$2") (pinfunction "2_P$2") (pintype "bidirectional"))
      (node (ref "U9") (pin "10") (pinfunction "SS_10") (pintype "bidirectional"))
    )
    (net (code "28") (name "Net-(C23-2)") (class "Default")
      (node (ref "C23") (pin "P$2") (pinfunction "2_P$2") (pintype "bidirectional"))
      (node (ref "R34") (pin "P$2") (pinfunction "2_P$2") (pintype "bidirectional"))
    )
    (net (code "29") (name "Net-(C24-2)") (class "Default")
      (node (ref "C24") (pin "P$2") (pinfunction "2_P$2") (pintype "bidirectional"))
      (node (ref "R34") (pin "P$1") (pinfunction "1_P$1") (pintype "bidirectional"))
      (node (ref "U9") (pin "3") (pinfunction "COMP_3") (pintype "bidirectional"))
    )
    (net (code "30") (name "Net-(IC2-GND)") (class "Default")
      (node (ref "IC2") (pin "4") (pinfunction "GND_4") (pintype "passive"))
      (node (ref "IOUT+") (pin "TP") (pinfunction "TP_TP") (pintype "input"))
      (node (ref "R1") (pin "P$1") (pinfunction "1_P$1") (pintype "bidirectional"))
      (node (ref "R2") (pin "P$1") (pinfunction "1_P$1") (pintype "bidirectional"))
      (node (ref "R3") (pin "P$1") (pinfunction "1_P$1") (pintype "bidirectional"))
      (node (ref "R4") (pin "P$1") (pinfunction "1_P$1") (pintype "bidirectional"))
      (node (ref "R5") (pin "P$1") (pinfunction "1_P$1") (pintype "bidirectional"))
      (node (ref "R6") (pin "P$1") (pinfunction "1_P$1") (pintype "bidirectional"))
      (node (ref "R7") (pin "P$1") (pinfunction "1_P$1") (pintype "bidirectional"))
      (node (ref "R9") (pin "1") (pinfunction "A_1") (pintype "passive"))
      (node (ref "R9") (pin "2") (pinfunction "S_2") (pintype "passive"))
    )
    (net (code "31") (name "Net-(IC2-VOUT)") (class "Default")
      (node (ref "IC2") (pin "6") (pinfunction "VOUT_6") (pintype "passive"))
      (node (ref "U1") (pin "4") (pinfunction "SET_4") (pintype "bidirectional"))
    )
    (net (code "32") (name "Net-(IC3A-C1+)") (class "Default")
      (node (ref "C1") (pin "+") (pinfunction "+_+") (pintype "passive"))
      (node (ref "IC3") (pin "7") (pinfunction "C1+_7") (pintype "passive"))
    )
    (net (code "33") (name "Net-(IC3A-C1-)") (class "Default")
      (node (ref "C1") (pin "-") (pinfunction "-_-") (pintype "passive"))
      (node (ref "IC3") (pin "1") (pinfunction "C1-_1") (pintype "passive"))
    )
    (net (code "34") (name "Net-(IC3A-C2+)") (class "Default")
      (node (ref "C2") (pin "+") (pinfunction "+_+") (pintype "passive"))
      (node (ref "IC3") (pin "2") (pinfunction "C2+_2") (pintype "passive"))
    )
    (net (code "35") (name "Net-(IC3A-C2-)") (class "Default")
      (node (ref "C2") (pin "-") (pinfunction "-_-") (pintype "passive"))
      (node (ref "IC3") (pin "3") (pinfunction "C2-_3") (pintype "passive"))
    )
    (net (code "36") (name "Net-(Q1-S)") (class "Default")
      (node (ref "Q1") (pin "123S") (pinfunction "S_123S") (pintype "passive"))
      (node (ref "R27") (pin "P$2") (pinfunction "2_P$2") (pintype "bidirectional"))
      (node (ref "R31") (pin "2") (pinfunction "2_2") (pintype "bidirectional"))
    )
    (net (code "37") (name "Net-(R1-2)") (class "Default")
      (node (ref "R1") (pin "P$2") (pinfunction "2_P$2") (pintype "bidirectional"))
      (node (ref "R2") (pin "P$2") (pinfunction "2_P$2") (pintype "bidirectional"))
      (node (ref "R3") (pin "P$2") (pinfunction "2_P$2") (pintype "bidirectional"))
      (node (ref "R4") (pin "P$2") (pinfunction "2_P$2") (pintype "bidirectional"))
      (node (ref "R5") (pin "P$2") (pinfunction "2_P$2") (pintype "bidirectional"))
      (node (ref "R6") (pin "P$2") (pinfunction "2_P$2") (pintype "bidirectional"))
      (node (ref "R7") (pin "P$2") (pinfunction "2_P$2") (pintype "bidirectional"))
      (node (ref "R8") (pin "P$2") (pinfunction "2_P$2") (pintype "bidirectional"))
      (node (ref "U1") (pin "1") (pinfunction "OUT_1") (pintype "bidirectional"))
      (node (ref "U1") (pin "2") (pinfunction "OUT_2") (pintype "bidirectional"))
      (node (ref "U1") (pin "3") (pinfunction "OUT_3") (pintype "bidirectional"))
      (node (ref "U1") (pin "9") (pinfunction "OUT_9") (pintype "bidirectional"))
    )
    (net (code "38") (name "Net-(R8-1)") (class "Default")
      (node (ref "R8") (pin "P$1") (pinfunction "1_P$1") (pintype "bidirectional"))
      (node (ref "R9") (pin "3") (pinfunction "E_3") (pintype "passive"))
    )
    (net (code "39") (name "Net-(R10-S)") (class "Default")
      (node (ref "R10") (pin "2") (pinfunction "S_2") (pintype "passive"))
      (node (ref "R11") (pin "P$2") (pinfunction "2_P$2") (pintype "bidirectional"))
    )
    (net (code "40") (name "Net-(R11-1)") (class "Default")
      (node (ref "R11") (pin "P$1") (pinfunction "1_P$1") (pintype "bidirectional"))
      (node (ref "R13") (pin "P$1") (pinfunction "1_P$1") (pintype "bidirectional"))
      (node (ref "U2") (pin "1") (pinfunction "REF_1") (pintype "input"))
    )
    (net (code "41") (name "Net-(R12-1)") (class "Default")
      (node (ref "R12") (pin "P$1") (pinfunction "1_P$1") (pintype "bidirectional"))
      (node (ref "U2") (pin "3") (pinfunction "+IN_3") (pintype "input"))
    )
    (net (code "42") (name "Net-(R12-2)") (class "Default")
      (node (ref "R12") (pin "P$2") (pinfunction "2_P$2") (pintype "bidirectional"))
      (node (ref "SENSE+") (pin "TP") (pinfunction "TP_TP") (pintype "input"))
    )
    (net (code "43") (name "Net-(R14-1)") (class "Default")
      (node (ref "R14") (pin "P$1") (pinfunction "1_P$1") (pintype "bidirectional"))
      (node (ref "U7") (pin "2") (pinfunction "OUT_2") (pintype "output"))
    )
    (net (code "44") (name "Net-(R17-2)") (class "Default")
      (node (ref "C7") (pin "2") (pinfunction "2_2") (pintype "bidirectional"))
      (node (ref "R17") (pin "P$2") (pinfunction "2_P$2") (pintype "bidirectional"))
    )
    (net (code "45") (name "Net-(R24-1)") (class "Default")
      (node (ref "R24") (pin "P$1") (pinfunction "1_P$1") (pintype "bidirectional"))
      (node (ref "R25") (pin "P$2") (pinfunction "2_P$2") (pintype "bidirectional"))
      (node (ref "U4") (pin "6") (pinfunction "FB_6") (pintype "bidirectional"))
    )
    (net (code "46") (name "Net-(R28-2)") (class "Default")
      (node (ref "R28") (pin "P$2") (pinfunction "2_P$2") (pintype "bidirectional"))
      (node (ref "U9") (pin "9") (pinfunction "RT_9") (pintype "bidirectional"))
    )
    (net (code "47") (name "Net-(R29-1)") (class "Default")
      (node (ref "R29") (pin "P$1") (pinfunction "1_P$1") (pintype "bidirectional"))
      (node (ref "R30") (pin "P$2") (pinfunction "2_P$2") (pintype "bidirectional"))
      (node (ref "U9") (pin "7") (pinfunction "UVLO_7") (pintype "bidirectional"))
    )
    (net (code "48") (name "Net-(U2--IN)") (class "Default")
      (node (ref "SENSE-") (pin "TP") (pinfunction "TP_TP") (pintype "input"))
      (node (ref "U2") (pin "2") (pinfunction "-IN_2") (pintype "input"))
    )
    (net (code "49") (name "Net-(U4-PG)") (class "Default")
      (node (ref "R23") (pin "1") (pinfunction "1_1") (pintype "bidirectional"))
      (node (ref "U4") (pin "7") (pinfunction "PG_7") (pintype "bidirectional"))
    )
    (net (code "50") (name "REF_BUF_IN-") (class "Default")
      (node (ref "R15") (pin "P$1") (pinfunction "1_P$1") (pintype "bidirectional"))
      (node (ref "U3") (pin "4") (pinfunction "-IN_4") (pintype "input"))
    )
    (net (code "51") (name "REF_BUF_OUT") (class "Default")
      (node (ref "R15") (pin "P$2") (pinfunction "2_P$2") (pintype "bidirectional"))
      (node (ref "R16") (pin "P$1") (pinfunction "1_P$1") (pintype "bidirectional"))
      (node (ref "U3") (pin "1") (pinfunction "OUT_1") (pintype "output"))
    )
    (net (code "52") (name "V-") (class "Default")
      (node (ref "U3") (pin "2") (pinfunction "V-_2") (pintype "power_in"))
    )
    (net (code "53") (name "unconnected-(ADC1-AVDD-Pad2)") (class "Default")
      (node (ref "ADC1") (pin "2") (pinfunction "AVDD_2") (pintype "bidirectional"))
    )
    (net (code "54") (name "unconnected-(ADC1-CONVST-Pad6)") (class "Default")
      (node (ref "ADC1") (pin "6") (pinfunction "CONVST_6") (pintype "bidirectional"))
    )
    (net (code "55") (name "unconnected-(ADC1-DIN-Pad9)") (class "Default")
      (node (ref "ADC1") (pin "9") (pinfunction "DIN_9") (pintype "bidirectional"))
    )
    (net (code "56") (name "unconnected-(ADC1-DOUT-Pad7)") (class "Default")
      (node (ref "ADC1") (pin "7") (pinfunction "DOUT_7") (pintype "bidirectional"))
    )
    (net (code "57") (name "unconnected-(ADC1-DVDD-Pad10)") (class "Default")
      (node (ref "ADC1") (pin "10") (pinfunction "DVDD_10") (pintype "bidirectional"))
    )
    (net (code "58") (name "unconnected-(ADC1-SCLK-Pad8)") (class "Default")
      (node (ref "ADC1") (pin "8") (pinfunction "SCLK_8") (pintype "bidirectional"))
    )
    (net (code "59") (name "unconnected-(IC1A-BOOT0-PadD6)") (class "Default")
      (node (ref "IC1") (pin "D6") (pinfunction "BOOT0_D6") (pintype "input"))
    )
    (net (code "60") (name "unconnected-(IC1A-BYPASS_REG-PadL4)") (class "Default")
      (node (ref "IC1") (pin "L4") (pinfunction "BYPASS_REG_L4") (pintype "input"))
    )
    (net (code "61") (name "unconnected-(IC1A-NRST-PadJ1)") (class "Default")
      (node (ref "IC1") (pin "J1") (pinfunction "NRST_J1") (pintype "bidirectional"))
    )
    (net (code "62") (name "unconnected-(IC1A-OSC_IN-PadG1)") (class "Default")
      (node (ref "IC1") (pin "G1") (pinfunction "OSC_IN_G1") (pintype "bidirectional"))
    )
    (net (code "63") (name "unconnected-(IC1A-OSC_OUT-PadH1)") (class "Default")
      (node (ref "IC1") (pin "H1") (pinfunction "OSC_OUT_H1") (pintype "bidirectional"))
    )
    (net (code "64") (name "unconnected-(IC1A-PA0-PadN3)") (class "Default")
      (node (ref "IC1") (pin "N3") (pinfunction "PA0_N3") (pintype "bidirectional"))
    )
    (net (code "65") (name "unconnected-(IC1A-PA1-PadN2)") (class "Default")
      (node (ref "IC1") (pin "N2") (pinfunction "PA1_N2") (pintype "bidirectional"))
    )
    (net (code "66") (name "unconnected-(IC1A-PA2-PadP2)") (class "Default")
      (node (ref "IC1") (pin "P2") (pinfunction "PA2_P2") (pintype "bidirectional"))
    )
    (net (code "67") (name "unconnected-(IC1A-PA3-PadR2)") (class "Default")
      (node (ref "IC1") (pin "R2") (pinfunction "PA3_R2") (pintype "bidirectional"))
    )
    (net (code "68") (name "unconnected-(IC1A-PA4-PadN4)") (class "Default")
      (node (ref "IC1") (pin "N4") (pinfunction "PA4_N4") (pintype "bidirectional"))
    )
    (net (code "69") (name "unconnected-(IC1A-PA5-PadP4)") (class "Default")
      (node (ref "IC1") (pin "P4") (pinfunction "PA5_P4") (pintype "bidirectional"))
    )
    (net (code "70") (name "unconnected-(IC1A-PA6-PadP3)") (class "Default")
      (node (ref "IC1") (pin "P3") (pinfunction "PA6_P3") (pintype "bidirectional"))
    )
    (net (code "71") (name "unconnected-(IC1A-PA7-PadR3)") (class "Default")
      (node (ref "IC1") (pin "R3") (pinfunction "PA7_R3") (pintype "bidirectional"))
    )
    (net (code "72") (name "unconnected-(IC1A-PA8-PadF15)") (class "Default")
      (node (ref "IC1") (pin "F15") (pinfunction "PA8_F15") (pintype "bidirectional"))
    )
    (net (code "73") (name "unconnected-(IC1A-PA9-PadE15)") (class "Default")
      (node (ref "IC1") (pin "E15") (pinfunction "PA9_E15") (pintype "bidirectional"))
    )
    (net (code "74") (name "unconnected-(IC1A-PA10-PadD15)") (class "Default")
      (node (ref "IC1") (pin "D15") (pinfunction "PA10_D15") (pintype "bidirectional"))
    )
    (net (code "75") (name "unconnected-(IC1A-PA11-PadC15)") (class "Default")
      (node (ref "IC1") (pin "C15") (pinfunction "PA11_C15") (pintype "bidirectional"))
    )
    (net (code "76") (name "unconnected-(IC1A-PA12-PadB15)") (class "Default")
      (node (ref "IC1") (pin "B15") (pinfunction "PA12_B15") (pintype "bidirectional"))
    )
    (net (code "77") (name "unconnected-(IC1A-PA13-PadA15)") (class "Default")
      (node (ref "IC1") (pin "A15") (pinfunction "PA13_A15") (pintype "bidirectional"))
    )
    (net (code "78") (name "unconnected-(IC1A-PA14-PadA14)") (class "Default")
      (node (ref "IC1") (pin "A14") (pinfunction "PA14_A14") (pintype "bidirectional"))
    )
    (net (code "79") (name "unconnected-(IC1A-PA15-PadA13)") (class "Default")
      (node (ref "IC1") (pin "A13") (pinfunction "PA15_A13") (pintype "bidirectional"))
    )
    (net (code "80") (name "unconnected-(IC1A-PB0-PadR5)") (class "Default")
      (node (ref "IC1") (pin "R5") (pinfunction "PB0_R5") (pintype "bidirectional"))
    )
    (net (code "81") (name "unconnected-(IC1A-PB1-PadR4)") (class "Default")
      (node (ref "IC1") (pin "R4") (pinfunction "PB1_R4") (pintype "bidirectional"))
    )
    (net (code "82") (name "unconnected-(IC1A-PB2-PadM6)") (class "Default")
      (node (ref "IC1") (pin "M6") (pinfunction "PB2_M6") (pintype "bidirectional"))
    )
    (net (code "83") (name "unconnected-(IC1A-PB3-PadA10)") (class "Default")
      (node (ref "IC1") (pin "A10") (pinfunction "PB3_A10") (pintype "bidirectional"))
    )
    (net (code "84") (name "unconnected-(IC1A-PB4-PadA9)") (class "Default")
      (node (ref "IC1") (pin "A9") (pinfunction "PB4_A9") (pintype "bidirectional"))
    )
    (net (code "85") (name "unconnected-(IC1A-PB5-PadA6)") (class "Default")
      (node (ref "IC1") (pin "A6") (pinfunction "PB5_A6") (pintype "bidirectional"))
    )
    (net (code "86") (name "unconnected-(IC1A-PB6-PadB6)") (class "Default")
      (node (ref "IC1") (pin "B6") (pinfunction "PB6_B6") (pintype "bidirectional"))
    )
    (net (code "87") (name "unconnected-(IC1A-PB7-PadB5)") (class "Default")
      (node (ref "IC1") (pin "B5") (pinfunction "PB7_B5") (pintype "bidirectional"))
    )
    (net (code "88") (name "unconnected-(IC1A-PB8-PadA5)") (class "Default")
      (node (ref "IC1") (pin "A5") (pinfunction "PB8_A5") (pintype "bidirectional"))
    )
    (net (code "89") (name "unconnected-(IC1A-PB9-PadB4)") (class "Default")
      (node (ref "IC1") (pin "B4") (pinfunction "PB9_B4") (pintype "bidirectional"))
    )
    (net (code "90") (name "unconnected-(IC1A-PB10-PadR12)") (class "Default")
      (node (ref "IC1") (pin "R12") (pinfunction "PB10_R12") (pintype "bidirectional"))
    )
    (net (code "91") (name "unconnected-(IC1A-PB11-PadR13)") (class "Default")
      (node (ref "IC1") (pin "R13") (pinfunction "PB11_R13") (pintype "bidirectional"))
    )
    (net (code "92") (name "unconnected-(IC1A-PB12-PadP12)") (class "Default")
      (node (ref "IC1") (pin "P12") (pinfunction "PB12_P12") (pintype "bidirectional"))
    )
    (net (code "93") (name "unconnected-(IC1A-PB13-PadP13)") (class "Default")
      (node (ref "IC1") (pin "P13") (pinfunction "PB13_P13") (pintype "bidirectional"))
    )
    (net (code "94") (name "unconnected-(IC1A-PB14-PadR14)") (class "Default")
      (node (ref "IC1") (pin "R14") (pinfunction "PB14_R14") (pintype "bidirectional"))
    )
    (net (code "95") (name "unconnected-(IC1A-PB15-PadR15)") (class "Default")
      (node (ref "IC1") (pin "R15") (pinfunction "PB15_R15") (pintype "bidirectional"))
    )
    (net (code "96") (name "unconnected-(IC1A-PC0-PadM2)") (class "Default")
      (node (ref "IC1") (pin "M2") (pinfunction "PC0_M2") (pintype "bidirectional"))
    )
    (net (code "97") (name "unconnected-(IC1A-PC1-PadM3)") (class "Default")
      (node (ref "IC1") (pin "M3") (pinfunction "PC1_M3") (pintype "bidirectional"))
    )
    (net (code "98") (name "unconnected-(IC1A-PC2-PadM4)") (class "Default")
      (node (ref "IC1") (pin "M4") (pinfunction "PC2_M4") (pintype "bidirectional"))
    )
    (net (code "99") (name "unconnected-(IC1A-PC3-PadM5)") (class "Default")
      (node (ref "IC1") (pin "M5") (pinfunction "PC3_M5") (pintype "bidirectional"))
    )
    (net (code "100") (name "unconnected-(IC1A-PC4-PadN5)") (class "Default")
      (node (ref "IC1") (pin "N5") (pinfunction "PC4_N5") (pintype "bidirectional"))
    )
    (net (code "101") (name "unconnected-(IC1A-PC5-PadP5)") (class "Default")
      (node (ref "IC1") (pin "P5") (pinfunction "PC5_P5") (pintype "bidirectional"))
    )
    (net (code "102") (name "unconnected-(IC1A-PC6-PadH15)") (class "Default")
      (node (ref "IC1") (pin "H15") (pinfunction "PC6_H15") (pintype "bidirectional"))
    )
    (net (code "103") (name "unconnected-(IC1A-PC7-PadG15)") (class "Default")
      (node (ref "IC1") (pin "G15") (pinfunction "PC7_G15") (pintype "bidirectional"))
    )
    (net (code "104") (name "unconnected-(IC1A-PC8-PadG14)") (class "Default")
      (node (ref "IC1") (pin "G14") (pinfunction "PC8_G14") (pintype "bidirectional"))
    )
    (net (code "105") (name "unconnected-(IC1A-PC9-PadF14)") (class "Default")
      (node (ref "IC1") (pin "F14") (pinfunction "PC9_F14") (pintype "bidirectional"))
    )
    (net (code "106") (name "unconnected-(IC1A-PC10-PadB14)") (class "Default")
      (node (ref "IC1") (pin "B14") (pinfunction "PC10_B14") (pintype "bidirectional"))
    )
    (net (code "107") (name "unconnected-(IC1A-PC11-PadB13)") (class "Default")
      (node (ref "IC1") (pin "B13") (pinfunction "PC11_B13") (pintype "bidirectional"))
    )
    (net (code "108") (name "unconnected-(IC1A-PC12-PadA12)") (class "Default")
      (node (ref "IC1") (pin "A12") (pinfunction "PC12_A12") (pintype "bidirectional"))
    )
    (net (code "109") (name "unconnected-(IC1A-PC13-PadD1)") (class "Default")
      (node (ref "IC1") (pin "D1") (pinfunction "PC13_D1") (pintype "bidirectional"))
    )
    (net (code "110") (name "unconnected-(IC1A-PC14-PadE1)") (class "Default")
      (node (ref "IC1") (pin "E1") (pinfunction "PC14_E1") (pintype "bidirectional"))
    )
    (net (code "111") (name "unconnected-(IC1A-PC15-PadF1)") (class "Default")
      (node (ref "IC1") (pin "F1") (pinfunction "PC15_F1") (pintype "bidirectional"))
    )
    (net (code "112") (name "unconnected-(IC1A-PD0-PadB12)") (class "Default")
      (node (ref "IC1") (pin "B12") (pinfunction "PD0_B12") (pintype "bidirectional"))
    )
    (net (code "113") (name "unconnected-(IC1A-PD1-PadC12)") (class "Default")
      (node (ref "IC1") (pin "C12") (pinfunction "PD1_C12") (pintype "bidirectional"))
    )
    (net (code "114") (name "unconnected-(IC1A-PD2-PadD12)") (class "Default")
      (node (ref "IC1") (pin "D12") (pinfunction "PD2_D12") (pintype "bidirectional"))
    )
    (net (code "115") (name "unconnected-(IC1A-PD3-PadD11)") (class "Default")
      (node (ref "IC1") (pin "D11") (pinfunction "PD3_D11") (pintype "bidirectional"))
    )
    (net (code "116") (name "unconnected-(IC1A-PD4-PadD10)") (class "Default")
      (node (ref "IC1") (pin "D10") (pinfunction "PD4_D10") (pintype "bidirectional"))
    )
    (net (code "117") (name "unconnected-(IC1A-PD5-PadC11)") (class "Default")
      (node (ref "IC1") (pin "C11") (pinfunction "PD5_C11") (pintype "bidirectional"))
    )
    (net (code "118") (name "unconnected-(IC1A-PD6-PadB11)") (class "Default")
      (node (ref "IC1") (pin "B11") (pinfunction "PD6_B11") (pintype "bidirectional"))
    )
    (net (code "119") (name "unconnected-(IC1A-PD7-PadA11)") (class "Default")
      (node (ref "IC1") (pin "A11") (pinfunction "PD7_A11") (pintype "bidirectional"))
    )
    (net (code "120") (name "unconnected-(IC1A-PD8-PadP15)") (class "Default")
      (node (ref "IC1") (pin "P15") (pinfunction "PD8_P15") (pintype "bidirectional"))
    )
    (net (code "121") (name "unconnected-(IC1A-PD9-PadP14)") (class "Default")
      (node (ref "IC1") (pin "P14") (pinfunction "PD9_P14") (pintype "bidirectional"))
    )
    (net (code "122") (name "unconnected-(IC1A-PD10-PadN15)") (class "Default")
      (node (ref "IC1") (pin "N15") (pinfunction "PD10_N15") (pintype "bidirectional"))
    )
    (net (code "123") (name "unconnected-(IC1A-PD11-PadN14)") (class "Default")
      (node (ref "IC1") (pin "N14") (pinfunction "PD11_N14") (pintype "bidirectional"))
    )
    (net (code "124") (name "unconnected-(IC1A-PD12-PadN13)") (class "Default")
      (node (ref "IC1") (pin "N13") (pinfunction "PD12_N13") (pintype "bidirectional"))
    )
    (net (code "125") (name "unconnected-(IC1A-PD13-PadM15)") (class "Default")
      (node (ref "IC1") (pin "M15") (pinfunction "PD13_M15") (pintype "bidirectional"))
    )
    (net (code "126") (name "unconnected-(IC1A-PD14-PadM14)") (class "Default")
      (node (ref "IC1") (pin "M14") (pinfunction "PD14_M14") (pintype "bidirectional"))
    )
    (net (code "127") (name "unconnected-(IC1A-PD15-PadL14)") (class "Default")
      (node (ref "IC1") (pin "L14") (pinfunction "PD15_L14") (pintype "bidirectional"))
    )
    (net (code "128") (name "unconnected-(IC1A-PDR_ON-PadC6)") (class "Default")
      (node (ref "IC1") (pin "C6") (pinfunction "PDR_ON_C6") (pintype "input"))
    )
    (net (code "129") (name "unconnected-(IC1A-PE0-PadA4)") (class "Default")
      (node (ref "IC1") (pin "A4") (pinfunction "PE0_A4") (pintype "bidirectional"))
    )
    (net (code "130") (name "unconnected-(IC1A-PE1-PadA3)") (class "Default")
      (node (ref "IC1") (pin "A3") (pinfunction "PE1_A3") (pintype "bidirectional"))
    )
    (net (code "131") (name "unconnected-(IC1A-PE2-PadA2)") (class "Default")
      (node (ref "IC1") (pin "A2") (pinfunction "PE2_A2") (pintype "bidirectional"))
    )
    (net (code "132") (name "unconnected-(IC1A-PE3-PadA1)") (class "Default")
      (node (ref "IC1") (pin "A1") (pinfunction "PE3_A1") (pintype "bidirectional"))
    )
    (net (code "133") (name "unconnected-(IC1A-PE4-PadB1)") (class "Default")
      (node (ref "IC1") (pin "B1") (pinfunction "PE4_B1") (pintype "bidirectional"))
    )
    (net (code "134") (name "unconnected-(IC1A-PE5-PadB2)") (class "Default")
      (node (ref "IC1") (pin "B2") (pinfunction "PE5_B2") (pintype "bidirectional"))
    )
    (net (code "135") (name "unconnected-(IC1A-PE6-PadB3)") (class "Default")
      (node (ref "IC1") (pin "B3") (pinfunction "PE6_B3") (pintype "bidirectional"))
    )
    (net (code "136") (name "unconnected-(IC1A-PE7-PadR8)") (class "Default")
      (node (ref "IC1") (pin "R8") (pinfunction "PE7_R8") (pintype "bidirectional"))
    )
    (net (code "137") (name "unconnected-(IC1A-PE8-PadP8)") (class "Default")
      (node (ref "IC1") (pin "P8") (pinfunction "PE8_P8") (pintype "bidirectional"))
    )
    (net (code "138") (name "unconnected-(IC1A-PE9-PadP9)") (class "Default")
      (node (ref "IC1") (pin "P9") (pinfunction "PE9_P9") (pintype "bidirectional"))
    )
    (net (code "139") (name "unconnected-(IC1A-PE10-PadR9)") (class "Default")
      (node (ref "IC1") (pin "R9") (pinfunction "PE10_R9") (pintype "bidirectional"))
    )
    (net (code "140") (name "unconnected-(IC1A-PE11-PadP10)") (class "Default")
      (node (ref "IC1") (pin "P10") (pinfunction "PE11_P10") (pintype "bidirectional"))
    )
    (net (code "141") (name "unconnected-(IC1A-PE12-PadR10)") (class "Default")
      (node (ref "IC1") (pin "R10") (pinfunction "PE12_R10") (pintype "bidirectional"))
    )
    (net (code "142") (name "unconnected-(IC1A-PE13-PadN11)") (class "Default")
      (node (ref "IC1") (pin "N11") (pinfunction "PE13_N11") (pintype "bidirectional"))
    )
    (net (code "143") (name "unconnected-(IC1A-PE14-PadP11)") (class "Default")
      (node (ref "IC1") (pin "P11") (pinfunction "PE14_P11") (pintype "bidirectional"))
    )
    (net (code "144") (name "unconnected-(IC1A-PE15-PadR11)") (class "Default")
      (node (ref "IC1") (pin "R11") (pinfunction "PE15_R11") (pintype "bidirectional"))
    )
    (net (code "145") (name "unconnected-(IC1A-PF0-PadE2)") (class "Default")
      (node (ref "IC1") (pin "E2") (pinfunction "PF0_E2") (pintype "bidirectional"))
    )
    (net (code "146") (name "unconnected-(IC1A-PF1-PadH3)") (class "Default")
      (node (ref "IC1") (pin "H3") (pinfunction "PF1_H3") (pintype "bidirectional"))
    )
    (net (code "147") (name "unconnected-(IC1A-PF2-PadH2)") (class "Default")
      (node (ref "IC1") (pin "H2") (pinfunction "PF2_H2") (pintype "bidirectional"))
    )
    (net (code "148") (name "unconnected-(IC1A-PF3-PadJ2)") (class "Default")
      (node (ref "IC1") (pin "J2") (pinfunction "PF3_J2") (pintype "bidirectional"))
    )
    (net (code "149") (name "unconnected-(IC1A-PF4-PadJ3)") (class "Default")
      (node (ref "IC1") (pin "J3") (pinfunction "PF4_J3") (pintype "bidirectional"))
    )
    (net (code "150") (name "unconnected-(IC1A-PF5-PadK3)") (class "Default")
      (node (ref "IC1") (pin "K3") (pinfunction "PF5_K3") (pintype "bidirectional"))
    )
    (net (code "151") (name "unconnected-(IC1A-PF6-PadK2)") (class "Default")
      (node (ref "IC1") (pin "K2") (pinfunction "PF6_K2") (pintype "bidirectional"))
    )
    (net (code "152") (name "unconnected-(IC1A-PF7-PadK1)") (class "Default")
      (node (ref "IC1") (pin "K1") (pinfunction "PF7_K1") (pintype "bidirectional"))
    )
    (net (code "153") (name "unconnected-(IC1A-PF8-PadL3)") (class "Default")
      (node (ref "IC1") (pin "L3") (pinfunction "PF8_L3") (pintype "bidirectional"))
    )
    (net (code "154") (name "unconnected-(IC1A-PF9-PadL2)") (class "Default")
      (node (ref "IC1") (pin "L2") (pinfunction "PF9_L2") (pintype "bidirectional"))
    )
    (net (code "155") (name "unconnected-(IC1A-PF10-PadL1)") (class "Default")
      (node (ref "IC1") (pin "L1") (pinfunction "PF10_L1") (pintype "bidirectional"))
    )
    (net (code "156") (name "unconnected-(IC1A-PF11-PadR6)") (class "Default")
      (node (ref "IC1") (pin "R6") (pinfunction "PF11_R6") (pintype "bidirectional"))
    )
    (net (code "157") (name "unconnected-(IC1A-PF12-PadP6)") (class "Default")
      (node (ref "IC1") (pin "P6") (pinfunction "PF12_P6") (pintype "bidirectional"))
    )
    (net (code "158") (name "unconnected-(IC1A-PF13-PadN6)") (class "Default")
      (node (ref "IC1") (pin "N6") (pinfunction "PF13_N6") (pintype "bidirectional"))
    )
    (net (code "159") (name "unconnected-(IC1A-PF14-PadR7)") (class "Default")
      (node (ref "IC1") (pin "R7") (pinfunction "PF14_R7") (pintype "bidirectional"))
    )
    (net (code "160") (name "unconnected-(IC1A-PF15-PadP7)") (class "Default")
      (node (ref "IC1") (pin "P7") (pinfunction "PF15_P7") (pintype "bidirectional"))
    )
    (net (code "161") (name "unconnected-(IC1A-PG0-PadN7)") (class "Default")
      (node (ref "IC1") (pin "N7") (pinfunction "PG0_N7") (pintype "bidirectional"))
    )
    (net (code "162") (name "unconnected-(IC1A-PG1-PadM7)") (class "Default")
      (node (ref "IC1") (pin "M7") (pinfunction "PG1_M7") (pintype "bidirectional"))
    )
    (net (code "163") (name "unconnected-(IC1A-PG2-PadL15)") (class "Default")
      (node (ref "IC1") (pin "L15") (pinfunction "PG2_L15") (pintype "bidirectional"))
    )
    (net (code "164") (name "unconnected-(IC1A-PG3-PadK15)") (class "Default")
      (node (ref "IC1") (pin "K15") (pinfunction "PG3_K15") (pintype "bidirectional"))
    )
    (net (code "165") (name "unconnected-(IC1A-PG4-PadK14)") (class "Default")
      (node (ref "IC1") (pin "K14") (pinfunction "PG4_K14") (pintype "bidirectional"))
    )
    (net (code "166") (name "unconnected-(IC1A-PG5-PadK13)") (class "Default")
      (node (ref "IC1") (pin "K13") (pinfunction "PG5_K13") (pintype "bidirectional"))
    )
    (net (code "167") (name "unconnected-(IC1A-PG6-PadJ15)") (class "Default")
      (node (ref "IC1") (pin "J15") (pinfunction "PG6_J15") (pintype "bidirectional"))
    )
    (net (code "168") (name "unconnected-(IC1A-PG7-PadJ14)") (class "Default")
      (node (ref "IC1") (pin "J14") (pinfunction "PG7_J14") (pintype "bidirectional"))
    )
    (net (code "169") (name "unconnected-(IC1A-PG8-PadH14)") (class "Default")
      (node (ref "IC1") (pin "H14") (pinfunction "PG8_H14") (pintype "bidirectional"))
    )
    (net (code "170") (name "unconnected-(IC1A-PG9-PadC10)") (class "Default")
      (node (ref "IC1") (pin "C10") (pinfunction "PG9_C10") (pintype "bidirectional"))
    )
    (net (code "171") (name "unconnected-(IC1A-PG10-PadB10)") (class "Default")
      (node (ref "IC1") (pin "B10") (pinfunction "PG10_B10") (pintype "bidirectional"))
    )
    (net (code "172") (name "unconnected-(IC1A-PG11-PadB9)") (class "Default")
      (node (ref "IC1") (pin "B9") (pinfunction "PG11_B9") (pintype "bidirectional"))
    )
    (net (code "173") (name "unconnected-(IC1A-PG12-PadB8)") (class "Default")
      (node (ref "IC1") (pin "B8") (pinfunction "PG12_B8") (pintype "bidirectional"))
    )
    (net (code "174") (name "unconnected-(IC1A-PG13-PadA8)") (class "Default")
      (node (ref "IC1") (pin "A8") (pinfunction "PG13_A8") (pintype "bidirectional"))
    )
    (net (code "175") (name "unconnected-(IC1A-PG14-PadA7)") (class "Default")
      (node (ref "IC1") (pin "A7") (pinfunction "PG14_A7") (pintype "bidirectional"))
    )
    (net (code "176") (name "unconnected-(IC1A-PG15-PadB7)") (class "Default")
      (node (ref "IC1") (pin "B7") (pinfunction "PG15_B7") (pintype "bidirectional"))
    )
    (net (code "177") (name "unconnected-(IC1A-PH2-PadF4)") (class "Default")
      (node (ref "IC1") (pin "F4") (pinfunction "PH2_F4") (pintype "bidirectional"))
    )
    (net (code "178") (name "unconnected-(IC1A-PH3-PadG4)") (class "Default")
      (node (ref "IC1") (pin "G4") (pinfunction "PH3_G4") (pintype "bidirectional"))
    )
    (net (code "179") (name "unconnected-(IC1A-PH4-PadH4)") (class "Default")
      (node (ref "IC1") (pin "H4") (pinfunction "PH4_H4") (pintype "bidirectional"))
    )
    (net (code "180") (name "unconnected-(IC1A-PH5-PadJ4)") (class "Default")
      (node (ref "IC1") (pin "J4") (pinfunction "PH5_J4") (pintype "bidirectional"))
    )
    (net (code "181") (name "unconnected-(IC1A-PH6-PadM11)") (class "Default")
      (node (ref "IC1") (pin "M11") (pinfunction "PH6_M11") (pintype "bidirectional"))
    )
    (net (code "182") (name "unconnected-(IC1A-PH7-PadN12)") (class "Default")
      (node (ref "IC1") (pin "N12") (pinfunction "PH7_N12") (pintype "bidirectional"))
    )
    (net (code "183") (name "unconnected-(IC1A-PH8-PadM12)") (class "Default")
      (node (ref "IC1") (pin "M12") (pinfunction "PH8_M12") (pintype "bidirectional"))
    )
    (net (code "184") (name "unconnected-(IC1A-PH9-PadM13)") (class "Default")
      (node (ref "IC1") (pin "M13") (pinfunction "PH9_M13") (pintype "bidirectional"))
    )
    (net (code "185") (name "unconnected-(IC1A-PH10-PadL13)") (class "Default")
      (node (ref "IC1") (pin "L13") (pinfunction "PH10_L13") (pintype "bidirectional"))
    )
    (net (code "186") (name "unconnected-(IC1A-PH11-PadL12)") (class "Default")
      (node (ref "IC1") (pin "L12") (pinfunction "PH11_L12") (pintype "bidirectional"))
    )
    (net (code "187") (name "unconnected-(IC1A-PH12-PadK12)") (class "Default")
      (node (ref "IC1") (pin "K12") (pinfunction "PH12_K12") (pintype "bidirectional"))
    )
    (net (code "188") (name "unconnected-(IC1A-PH13-PadE12)") (class "Default")
      (node (ref "IC1") (pin "E12") (pinfunction "PH13_E12") (pintype "bidirectional"))
    )
    (net (code "189") (name "unconnected-(IC1A-PH14-PadE13)") (class "Default")
      (node (ref "IC1") (pin "E13") (pinfunction "PH14_E13") (pintype "bidirectional"))
    )
    (net (code "190") (name "unconnected-(IC1A-PH15-PadD13)") (class "Default")
      (node (ref "IC1") (pin "D13") (pinfunction "PH15_D13") (pintype "bidirectional"))
    )
    (net (code "191") (name "unconnected-(IC1A-PI0-PadE14)") (class "Default")
      (node (ref "IC1") (pin "E14") (pinfunction "PI0_E14") (pintype "bidirectional"))
    )
    (net (code "192") (name "unconnected-(IC1A-PI1-PadD14)") (class "Default")
      (node (ref "IC1") (pin "D14") (pinfunction "PI1_D14") (pintype "bidirectional"))
    )
    (net (code "193") (name "unconnected-(IC1A-PI2-PadC14)") (class "Default")
      (node (ref "IC1") (pin "C14") (pinfunction "PI2_C14") (pintype "bidirectional"))
    )
    (net (code "194") (name "unconnected-(IC1A-PI3-PadC13)") (class "Default")
      (node (ref "IC1") (pin "C13") (pinfunction "PI3_C13") (pintype "bidirectional"))
    )
    (net (code "195") (name "unconnected-(IC1A-PI4-PadD4)") (class "Default")
      (node (ref "IC1") (pin "D4") (pinfunction "PI4_D4") (pintype "bidirectional"))
    )
    (net (code "196") (name "unconnected-(IC1A-PI5-PadC4)") (class "Default")
      (node (ref "IC1") (pin "C4") (pinfunction "PI5_C4") (pintype "bidirectional"))
    )
    (net (code "197") (name "unconnected-(IC1A-PI6-PadC3)") (class "Default")
      (node (ref "IC1") (pin "C3") (pinfunction "PI6_C3") (pintype "bidirectional"))
    )
    (net (code "198") (name "unconnected-(IC1A-PI7-PadC2)") (class "Default")
      (node (ref "IC1") (pin "C2") (pinfunction "PI7_C2") (pintype "bidirectional"))
    )
    (net (code "199") (name "unconnected-(IC1A-PI8-PadD2)") (class "Default")
      (node (ref "IC1") (pin "D2") (pinfunction "PI8_D2") (pintype "bidirectional"))
    )
    (net (code "200") (name "unconnected-(IC1A-PI9-PadD3)") (class "Default")
      (node (ref "IC1") (pin "D3") (pinfunction "PI9_D3") (pintype "bidirectional"))
    )
    (net (code "201") (name "unconnected-(IC1A-PI10-PadE3)") (class "Default")
      (node (ref "IC1") (pin "E3") (pinfunction "PI10_E3") (pintype "bidirectional"))
    )
    (net (code "202") (name "unconnected-(IC1A-PI11-PadE4)") (class "Default")
      (node (ref "IC1") (pin "E4") (pinfunction "PI11_E4") (pintype "bidirectional"))
    )
    (net (code "203") (name "unconnected-(IC1A-VBAT-PadC1)") (class "Default")
      (node (ref "IC1") (pin "C1") (pinfunction "VBAT_C1") (pintype "power_in"))
    )
    (net (code "204") (name "unconnected-(IC1A-VCAP1-PadM10)") (class "Default")
      (node (ref "IC1") (pin "M10") (pinfunction "VCAP1_M10") (pintype "power_in"))
    )
    (net (code "205") (name "unconnected-(IC1A-VCAP2-PadF13)") (class "Default")
      (node (ref "IC1") (pin "F13") (pinfunction "VCAP2_F13") (pintype "power_in"))
    )
    (net (code "206") (name "unconnected-(IC1A-VDDA-PadR1)") (class "Default")
      (node (ref "IC1") (pin "R1") (pinfunction "VDDA_R1") (pintype "power_in"))
    )
    (net (code "207") (name "unconnected-(IC1A-VREF+-PadP1)") (class "Default")
      (node (ref "IC1") (pin "P1") (pinfunction "VREF+_P1") (pintype "power_in"))
    )
    (net (code "208") (name "unconnected-(IC1A-VREF--PadN1)") (class "Default")
      (node (ref "IC1") (pin "N1") (pinfunction "VREF-_N1") (pintype "power_in"))
    )
    (net (code "209") (name "unconnected-(IC1A-VSSA-PadM1)") (class "Default")
      (node (ref "IC1") (pin "M1") (pinfunction "VSSA_M1") (pintype "power_in"))
    )
    (net (code "210") (name "unconnected-(REG1-IN-Pad1)") (class "Default")
      (node (ref "REG1") (pin "1") (pinfunction "IN_1") (pintype "bidirectional"))
    )
    (net (code "211") (name "unconnected-(U2-NIC-Pad8)") (class "Default")
      (node (ref "U2") (pin "8") (pinfunction "NIC_8") (pintype "no_connect"))
    )
    (net (code "212") (name "unconnected-(U8-IN+-Pad1)") (class "Default")
      (node (ref "U8") (pin "1") (pinfunction "IN+_1") (pintype "bidirectional"))
    )
    (net (code "213") (name "unconnected-(U8-OUT-Pad4)") (class "Default")
      (node (ref "U8") (pin "4") (pinfunction "OUT_4") (pintype "bidirectional"))
    )
  )
)
